# rfid_chip_evaluation.net
KiCad netlist of a schematic drawn in Altium Designer
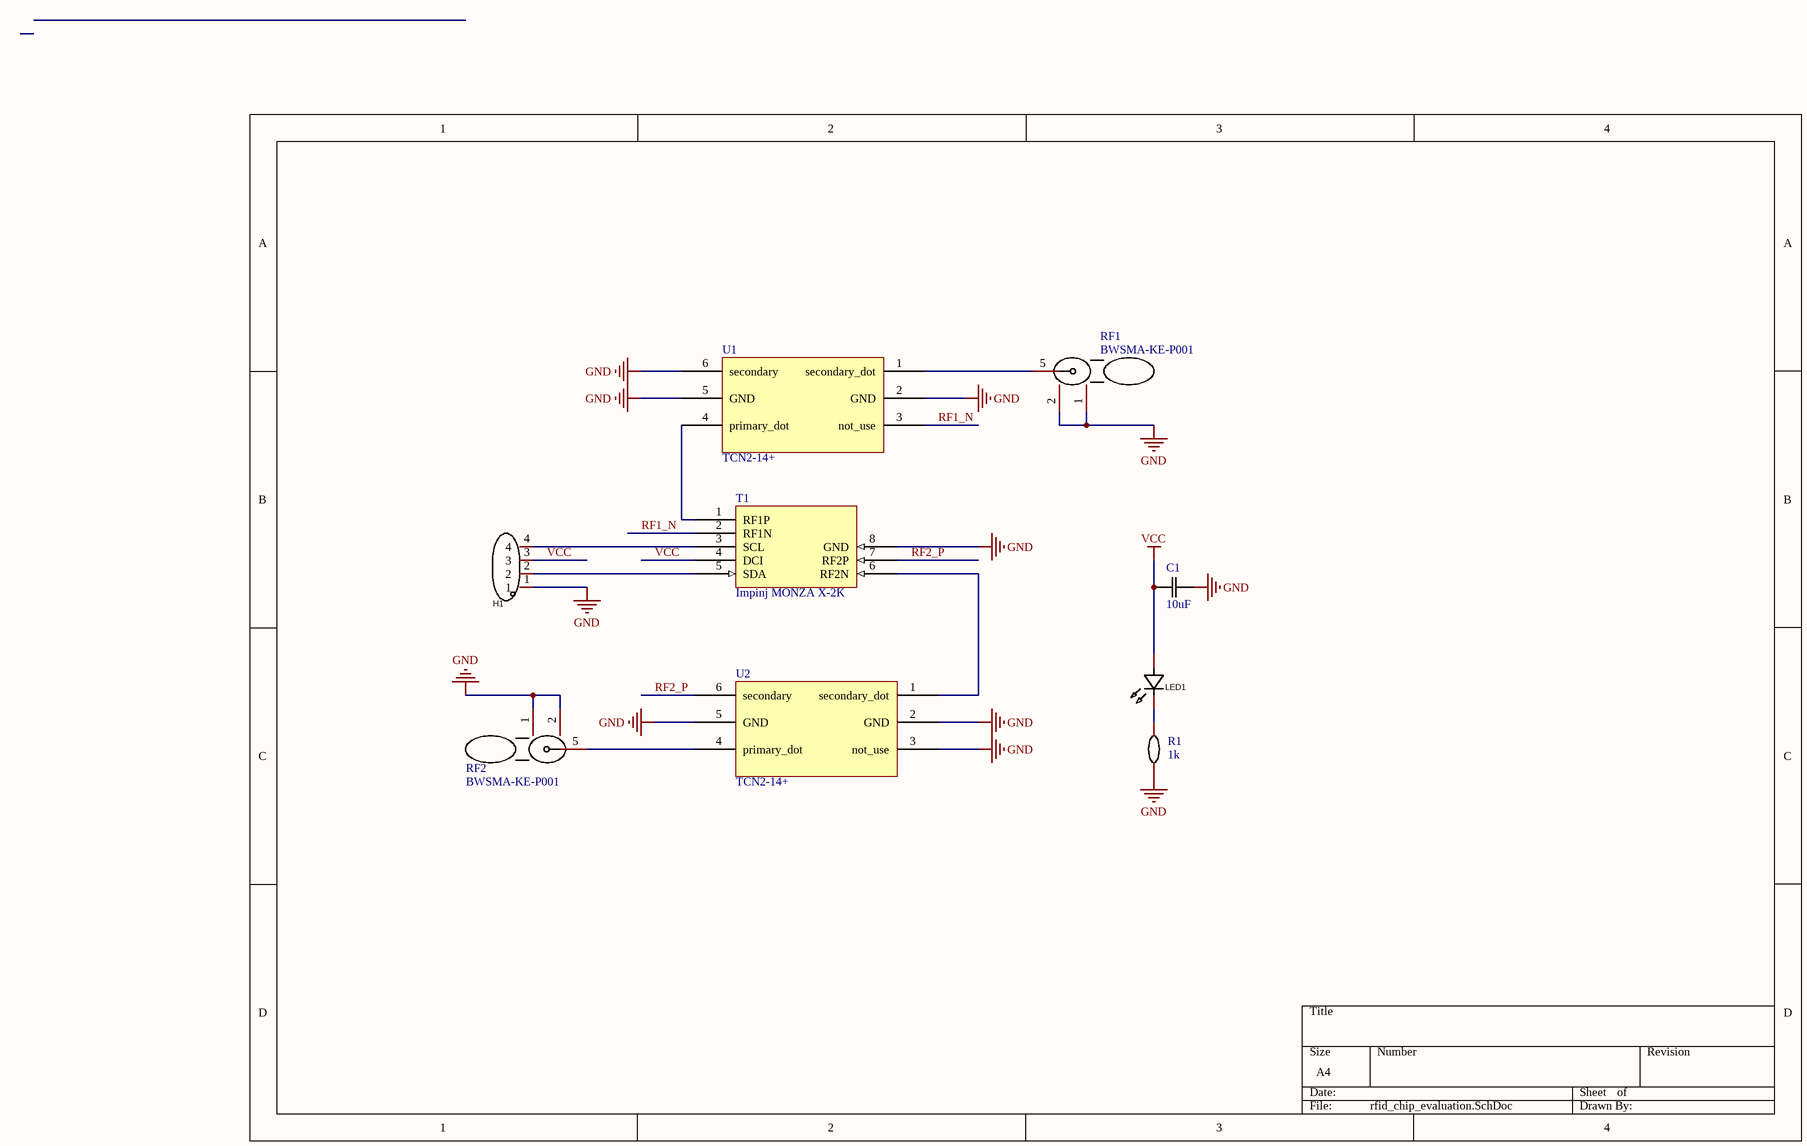
[diagram p0: rfid_chip_evaluation.SchDoc]

(export (version "E")
  (design (tool "Eeschema 10.0.6"))
  (components
    (comp (ref "C1")
      (value "10uF")
      (footprint "CAP_CL10_SAM")
      (description "10 uF Capacity")
      (fields
        (field (name "MANUFACTURER_PART_NUMBER") "CL10A106KP8NNNC")
        (field (name "COPYRIGHT") "Copyright (C) 2023 Ultra Librarian. All rights reserved.")
      )
      (libsource (lib "RF_selector") (part "CL10A106KP8NNNC"))
    )
    (comp (ref "H1")
      (value "PZ254V-11-04P_C492403")
      (footprint "HDR-TH_4P-P2.54-V-M")
      (fields (field (name "MANUFACTURER") "XFCN(兴飞)") (field (name "MANUFACTURER PART") "PZ254V-11-04P"))
      (libsource (lib "Schlib1") (part "PZ254V-11-04P_C492403"))
    )
    (comp (ref "LED1")
      (value "XL-1005UGC")
      (footprint "LED0402-RD_GREEN")
      (description "正贴发光二极管 翠绿")
      (fields (field (name "MANUFACTURER") "XINGLIGHT(成兴光)"))
      (libsource (lib "Schlib1") (part "XL-1005UGC"))
    )
    (comp (ref "R1")
      (value "1k")
      (footprint "R0402")
      (description "电阻类型:厚膜电阻;阻值:1.21kΩ;精度:±1%;功率:100mW;温度系数:±100ppm/℃;最大工作电压:75V;工作温度范围:-55℃~+155℃;")
      (fields (field (name "MANUFACTURER") "KOA") (field (name "MANUFACTURER PART") "RK73H1ETTP1211F"))
      (libsource (lib "RF_selector") (part "RK73H1ETTP1211F"))
    )
    (comp (ref "RF1")
      (value "BWSMA-KE-P001")
      (footprint "SMA-SMD_BWSMA-KE-P001")
      (description "连接器类型:板端;射频系列:SMA;接口类型:内孔;端口数量:1;阻抗:-;频率-最大值:-;样式:偏脚;接口直径:5.2mm;接口长度/高度:-;工作温度范围:-;")
      (fields (field (name "MANUFACTURER") "BAT WIRELESS(蝙蝠无线)"))
      (libsource (lib "RF_selector") (part "BWSMA-KE-P001"))
    )
    (comp (ref "RF2")
      (value "BWSMA-KE-P001")
      (footprint "SMA-SMD_BWSMA-KE-P001")
      (description "连接器类型:板端;射频系列:SMA;接口类型:内孔;端口数量:1;阻抗:-;频率-最大值:-;样式:偏脚;接口直径:5.2mm;接口长度/高度:-;工作温度范围:-;")
      (fields (field (name "MANUFACTURER") "BAT WIRELESS(蝙蝠无线)"))
      (libsource (lib "RF_selector") (part "BWSMA-KE-P001"))
    )
    (comp (ref "T1")
      (value "Impinj MONZA X-2K")
      (footprint "IPJX2K")
      (description "Impinj MONZA X-2K RFID tag chip")
      (libsource (lib "Schlib1") (part "Impinj MONZA X-2K"))
    )
    (comp (ref "U1")
      (value "TCN2-14+")
      (footprint "FV1206-1")
      (description "balun 700MHz to 1400MHz 1:1")
      (libsource (lib "Schlib1") (part "TCN2-14+"))
    )
    (comp (ref "U2")
      (value "TCN2-14+")
      (footprint "FV1206-1")
      (description "balun 700MHz to 1400MHz 1:1")
      (libsource (lib "Schlib1") (part "TCN2-14+"))
    )
  )
  (nets
    (net (code "1") (name "/RF1_N") (class "Default")
      (node (ref "T1") (pin "2") (pinfunction "RF1N_2") (pintype "passive"))
      (node (ref "U1") (pin "3") (pinfunction "not_use_3") (pintype "passive"))
    )
    (net (code "2") (name "/RF2_P") (class "Default")
      (node (ref "T1") (pin "7") (pinfunction "RF2P_7") (pintype "input"))
      (node (ref "U2") (pin "6") (pinfunction "secondary_6") (pintype "passive"))
    )
    (net (code "3") (name "GND") (class "Default")
      (node (ref "C1") (pin "2") (pinfunction "2_2") (pintype "passive"))
      (node (ref "H1") (pin "1") (pinfunction "1_1") (pintype "passive"))
      (node (ref "R1") (pin "1") (pinfunction "1_1") (pintype "passive"))
      (node (ref "RF1") (pin "1") (pinfunction "1_1") (pintype "passive"))
      (node (ref "RF1") (pin "2") (pinfunction "2_2") (pintype "passive"))
      (node (ref "RF2") (pin "1") (pinfunction "1_1") (pintype "passive"))
      (node (ref "RF2") (pin "2") (pinfunction "2_2") (pintype "passive"))
      (node (ref "T1") (pin "8") (pinfunction "GND_8") (pintype "input"))
      (node (ref "U1") (pin "2") (pinfunction "GND_2") (pintype "passive"))
      (node (ref "U1") (pin "5") (pinfunction "GND_5") (pintype "passive"))
      (node (ref "U1") (pin "6") (pinfunction "secondary_6") (pintype "passive"))
      (node (ref "U2") (pin "2") (pinfunction "GND_2") (pintype "passive"))
      (node (ref "U2") (pin "3") (pinfunction "not_use_3") (pintype "passive"))
      (node (ref "U2") (pin "5") (pinfunction "GND_5") (pintype "passive"))
    )
    (net (code "4") (name "Net-(LED1-K)") (class "Default")
      (node (ref "LED1") (pin "1") (pinfunction "K_1") (pintype "passive"))
      (node (ref "R1") (pin "2") (pinfunction "2_2") (pintype "passive"))
    )
    (net (code "5") (name "Net-(T1-RF1P)") (class "Default")
      (node (ref "T1") (pin "1") (pinfunction "RF1P_1") (pintype "passive"))
      (node (ref "U1") (pin "4") (pinfunction "primary_dot_4") (pintype "passive"))
    )
    (net (code "6") (name "Net-(T1-RF2N)") (class "Default")
      (node (ref "T1") (pin "6") (pinfunction "RF2N_6") (pintype "input"))
      (node (ref "U2") (pin "1") (pinfunction "secondary_dot_1") (pintype "passive"))
    )
    (net (code "7") (name "Net-(T1-SCL)") (class "Default")
      (node (ref "H1") (pin "4") (pinfunction "4_4") (pintype "passive"))
      (node (ref "T1") (pin "3") (pinfunction "SCL_3") (pintype "passive"))
    )
    (net (code "8") (name "Net-(T1-SDA)") (class "Default")
      (node (ref "H1") (pin "2") (pinfunction "2_2") (pintype "passive"))
      (node (ref "T1") (pin "5") (pinfunction "SDA_5") (pintype "input"))
    )
    (net (code "9") (name "Net-(U1-secondary_dot)") (class "Default")
      (node (ref "RF1") (pin "5") (pinfunction "5_5") (pintype "passive"))
      (node (ref "U1") (pin "1") (pinfunction "secondary_dot_1") (pintype "passive"))
    )
    (net (code "10") (name "Net-(U2-primary_dot)") (class "Default")
      (node (ref "RF2") (pin "5") (pinfunction "5_5") (pintype "passive"))
      (node (ref "U2") (pin "4") (pinfunction "primary_dot_4") (pintype "passive"))
    )
    (net (code "11") (name "VCC") (class "Default")
      (node (ref "C1") (pin "1") (pinfunction "1_1") (pintype "passive"))
      (node (ref "H1") (pin "3") (pinfunction "3_3") (pintype "passive"))
      (node (ref "LED1") (pin "2") (pinfunction "A_2") (pintype "passive"))
      (node (ref "T1") (pin "4") (pinfunction "DCI_4") (pintype "passive"))
    )
  )
)
